# Clock_Timer.net
KiCad netlist of a schematic drawn in EAGLE
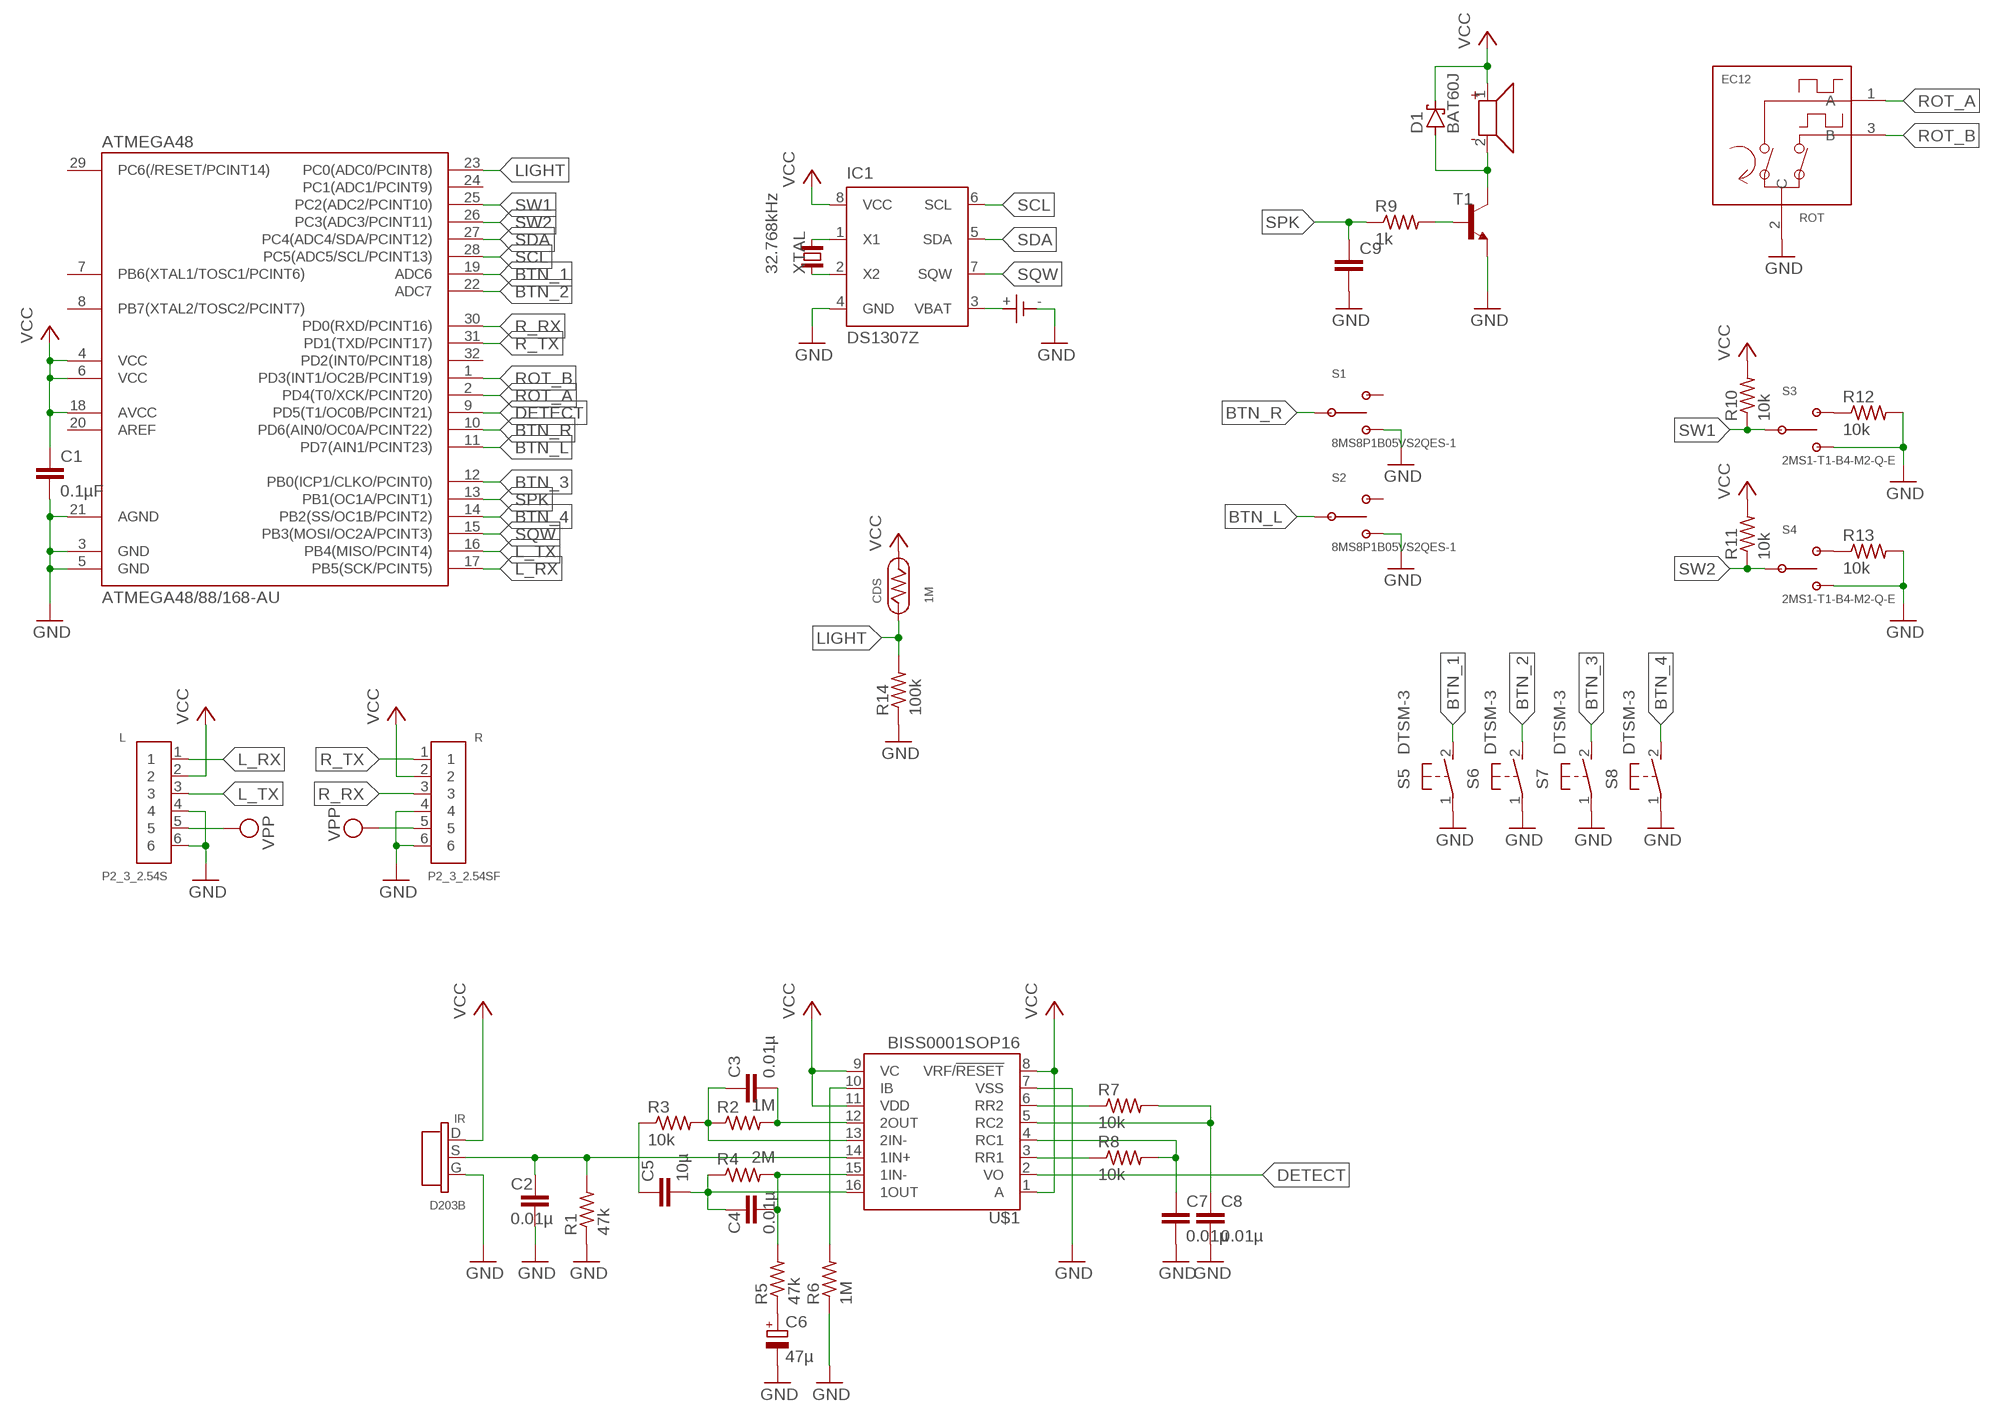
[diagram p0: schematic, sheet 1]

(export (version "E")
  (design (tool "Eeschema 10.0.6"))
  (components
    (comp (ref "ATMEGA48")
      (value "ATMEGA48/88/168-AU")
      (footprint "eagle-import:TQFP32-08")
      (libsource (lib "eagle-import") (part "ATMEGA48/88/168-AU"))
    )
    (comp (ref "BAT")
      (value "BC1/3N")
      (footprint "eagle-import:BC1_3N")
      (libsource (lib "eagle-import") (part "BC1/3N"))
    )
    (comp (ref "C1")
      (value "0.1µF")
      (footprint "eagle-import:C0603")
      (libsource (lib "eagle-import") (part "C-EUC0603"))
    )
    (comp (ref "C2")
      (value "0.01µ")
      (footprint "eagle-import:C0603")
      (libsource (lib "eagle-import") (part "resistor_348_C-EUC0603"))
    )
    (comp (ref "C3")
      (value "0.01µ")
      (footprint "eagle-import:C0603")
      (libsource (lib "eagle-import") (part "resistor_348_C-EUC0603"))
    )
    (comp (ref "C4")
      (value "0.01µ")
      (footprint "eagle-import:C0603")
      (libsource (lib "eagle-import") (part "resistor_348_C-EUC0603"))
    )
    (comp (ref "C5")
      (value "10µ")
      (footprint "eagle-import:C0603")
      (libsource (lib "eagle-import") (part "resistor_348_C-EUC0603"))
    )
    (comp (ref "C6")
      (value "47µ")
      (footprint "eagle-import:153CLV-0605")
      (libsource (lib "eagle-import") (part "CPOL-EU153CLV-0605"))
    )
    (comp (ref "C7")
      (value "0.01µ")
      (footprint "eagle-import:C0603")
      (libsource (lib "eagle-import") (part "resistor_348_C-EUC0603"))
    )
    (comp (ref "C8")
      (value "0.01µ")
      (footprint "eagle-import:C0603")
      (libsource (lib "eagle-import") (part "resistor_348_C-EUC0603"))
    )
    (comp (ref "C9")
      (value "C-EUC0603")
      (footprint "eagle-import:C0603")
      (libsource (lib "eagle-import") (part "resistor_348_C-EUC0603"))
    )
    (comp (ref "CDS")
      (value "1M")
      (footprint "eagle-import:GL55")
      (libsource (lib "eagle-import") (part "GL55"))
    )
    (comp (ref "D1")
      (value "BAT60J")
      (footprint "eagle-import:SOD323_ST")
      (libsource (lib "eagle-import") (part "BAT60J"))
    )
    (comp (ref "IC1")
      (value "DS1307Z")
      (footprint "eagle-import:SOIC8")
      (libsource (lib "eagle-import") (part "DS1307Z"))
    )
    (comp (ref "IR")
      (value "D203B")
      (footprint "eagle-import:D203B")
      (libsource (lib "eagle-import") (part "D203B"))
    )
    (comp (ref "L")
      (value "P2_3_2.54S")
      (footprint "eagle-import:P2_3_2.54S")
      (libsource (lib "eagle-import") (part "P2_3_2.54S"))
    )
    (comp (ref "R")
      (value "P2_3_2.54SF")
      (footprint "eagle-import:P2_3_2.54SF")
      (libsource (lib "eagle-import") (part "P2_3_2.54SF"))
    )
    (comp (ref "R1")
      (value "47k")
      (footprint "eagle-import:R0603")
      (libsource (lib "eagle-import") (part "R-US_R0603"))
    )
    (comp (ref "R2")
      (value "1M")
      (footprint "eagle-import:R0603")
      (libsource (lib "eagle-import") (part "R-US_R0603"))
    )
    (comp (ref "R3")
      (value "10k")
      (footprint "eagle-import:R0603")
      (libsource (lib "eagle-import") (part "R-US_R0603"))
    )
    (comp (ref "R4")
      (value "2M")
      (footprint "eagle-import:R0603")
      (libsource (lib "eagle-import") (part "R-US_R0603"))
    )
    (comp (ref "R5")
      (value "47k")
      (footprint "eagle-import:R0603")
      (libsource (lib "eagle-import") (part "R-US_R0603"))
    )
    (comp (ref "R6")
      (value "1M")
      (footprint "eagle-import:R0603")
      (libsource (lib "eagle-import") (part "R-US_R0603"))
    )
    (comp (ref "R7")
      (value "10k")
      (footprint "eagle-import:R0603")
      (libsource (lib "eagle-import") (part "R-US_R0603"))
    )
    (comp (ref "R8")
      (value "10k")
      (footprint "eagle-import:R0603")
      (libsource (lib "eagle-import") (part "R-US_R0603"))
    )
    (comp (ref "R9")
      (value "1k")
      (footprint "eagle-import:R0603")
      (libsource (lib "eagle-import") (part "resistor_348_R-US_R0603"))
    )
    (comp (ref "R10")
      (value "10k")
      (footprint "eagle-import:R0603")
      (libsource (lib "eagle-import") (part "R-US_R0603"))
    )
    (comp (ref "R11")
      (value "10k")
      (footprint "eagle-import:R0603")
      (libsource (lib "eagle-import") (part "R-US_R0603"))
    )
    (comp (ref "R12")
      (value "10k")
      (footprint "eagle-import:R0603")
      (libsource (lib "eagle-import") (part "R-US_R0603"))
    )
    (comp (ref "R13")
      (value "10k")
      (footprint "eagle-import:R0603")
      (libsource (lib "eagle-import") (part "R-US_R0603"))
    )
    (comp (ref "R14")
      (value "100k")
      (footprint "eagle-import:R0603")
      (libsource (lib "eagle-import") (part "R-US_R0603"))
    )
    (comp (ref "ROT")
      (value "EC12")
      (footprint "eagle-import:EC12")
      (libsource (lib "eagle-import") (part "EC12"))
    )
    (comp (ref "S1")
      (value "8MS8P1B05VS2QES-1")
      (footprint "eagle-import:8MS8P1B05VS2QES-1")
      (libsource (lib "eagle-import") (part "8MS8P1B05VS2QES-1"))
    )
    (comp (ref "S2")
      (value "8MS8P1B05VS2QES-1")
      (footprint "eagle-import:8MS8P1B05VS2QES-1")
      (libsource (lib "eagle-import") (part "8MS8P1B05VS2QES-1"))
    )
    (comp (ref "S3")
      (value "2MS1-T1-B4-M2-Q-E")
      (footprint "eagle-import:2MS1-T1-B4-M2-Q-E")
      (libsource (lib "eagle-import") (part "2MS1-T1-B4-M2-Q-E"))
    )
    (comp (ref "S4")
      (value "2MS1-T1-B4-M2-Q-E")
      (footprint "eagle-import:2MS1-T1-B4-M2-Q-E")
      (libsource (lib "eagle-import") (part "2MS1-T1-B4-M2-Q-E"))
    )
    (comp (ref "S5")
      (value "DTSM-3")
      (footprint "eagle-import:DTSM-3")
      (libsource (lib "eagle-import") (part "DTSM-3"))
    )
    (comp (ref "S6")
      (value "DTSM-3")
      (footprint "eagle-import:DTSM-3")
      (libsource (lib "eagle-import") (part "DTSM-3"))
    )
    (comp (ref "S7")
      (value "DTSM-3")
      (footprint "eagle-import:DTSM-3")
      (libsource (lib "eagle-import") (part "DTSM-3"))
    )
    (comp (ref "S8")
      (value "DTSM-3")
      (footprint "eagle-import:DTSM-3")
      (libsource (lib "eagle-import") (part "DTSM-3"))
    )
    (comp (ref "T1")
      (value "-NPN-SOT23-EBC")
      (footprint "eagle-import:SOT23-EBC")
      (libsource (lib "eagle-import") (part "-NPN-SOT23-EBC"))
    )
    (comp (ref "U$1")
      (value "BISS0001SOP16")
      (footprint "eagle-import:SOP16")
      (libsource (lib "eagle-import") (part "BISS0001SOP16"))
    )
    (comp (ref "U$9")
      (value "UGCM0903EPD")
      (footprint "eagle-import:UGCM0903EPD")
      (libsource (lib "eagle-import") (part "UGCM0903EPD"))
    )
    (comp (ref "XTAL")
      (value "32.768kHz")
      (footprint "eagle-import:FC-255")
      (libsource (lib "eagle-import") (part "CRYTALFC-255"))
    )
  )
  (nets
    (net (code "1") (name "BTN_1") (class "Default")
      (node (ref "ATMEGA48") (pin "19") (pinfunction "ADC6_19") (pintype "passive"))
      (node (ref "S5") (pin "2") (pinfunction "2_2") (pintype "passive"))
    )
    (net (code "2") (name "BTN_2") (class "Default")
      (node (ref "ATMEGA48") (pin "22") (pinfunction "ADC7_22") (pintype "passive"))
      (node (ref "S6") (pin "2") (pinfunction "2_2") (pintype "passive"))
    )
    (net (code "3") (name "BTN_3") (class "Default")
      (node (ref "ATMEGA48") (pin "12") (pinfunction "PB0(ICP1/CLKO/PCINT0)_12") (pintype "bidirectional"))
      (node (ref "S7") (pin "2") (pinfunction "2_2") (pintype "passive"))
    )
    (net (code "4") (name "BTN_4") (class "Default")
      (node (ref "ATMEGA48") (pin "14") (pinfunction "PB2(SS/OC1B/PCINT2)_14") (pintype "bidirectional"))
      (node (ref "S8") (pin "2") (pinfunction "2_2") (pintype "passive"))
    )
    (net (code "5") (name "BTN_L") (class "Default")
      (node (ref "ATMEGA48") (pin "11") (pinfunction "PD7(AIN1/PCINT23)_11") (pintype "bidirectional"))
      (node (ref "S2") (pin "2") (pinfunction "C_2") (pintype "bidirectional"))
    )
    (net (code "6") (name "BTN_R") (class "Default")
      (node (ref "ATMEGA48") (pin "10") (pinfunction "PD6(AIN0/OC0A/PCINT22)_10") (pintype "bidirectional"))
      (node (ref "S1") (pin "2") (pinfunction "C_2") (pintype "bidirectional"))
    )
    (net (code "7") (name "DETECT") (class "Default")
      (node (ref "ATMEGA48") (pin "9") (pinfunction "PD5(T1/OC0B/PCINT21)_9") (pintype "bidirectional"))
      (node (ref "U$1") (pin "2") (pinfunction "VO_2") (pintype "bidirectional"))
    )
    (net (code "8") (name "GND") (class "Default")
      (node (ref "ATMEGA48") (pin "21") (pinfunction "AGND_21") (pintype "power_in"))
      (node (ref "ATMEGA48") (pin "3") (pinfunction "GND_3") (pintype "power_in"))
      (node (ref "ATMEGA48") (pin "5") (pinfunction "GND_5") (pintype "power_in"))
      (node (ref "BAT") (pin "-") (pinfunction "V-_-") (pintype "power_in"))
      (node (ref "C1") (pin "2") (pinfunction "2_2") (pintype "passive"))
      (node (ref "C2") (pin "2") (pinfunction "2_2") (pintype "passive"))
      (node (ref "C6") (pin "-") (pinfunction "-_-") (pintype "passive"))
      (node (ref "C7") (pin "2") (pinfunction "2_2") (pintype "passive"))
      (node (ref "C8") (pin "2") (pinfunction "2_2") (pintype "passive"))
      (node (ref "C9") (pin "2") (pinfunction "2_2") (pintype "passive"))
      (node (ref "IC1") (pin "4") (pinfunction "GND_4") (pintype "power_in"))
      (node (ref "IR") (pin "G") (pinfunction "GND_G") (pintype "bidirectional"))
      (node (ref "L") (pin "4") (pinfunction "4_4") (pintype "bidirectional"))
      (node (ref "L") (pin "6") (pinfunction "6_6") (pintype "bidirectional"))
      (node (ref "R") (pin "4") (pinfunction "4_4") (pintype "bidirectional"))
      (node (ref "R") (pin "6") (pinfunction "6_6") (pintype "bidirectional"))
      (node (ref "R1") (pin "1") (pinfunction "1_1") (pintype "passive"))
      (node (ref "R12") (pin "2") (pinfunction "2_2") (pintype "passive"))
      (node (ref "R13") (pin "2") (pinfunction "2_2") (pintype "passive"))
      (node (ref "R14") (pin "1") (pinfunction "1_1") (pintype "passive"))
      (node (ref "R6") (pin "1") (pinfunction "1_1") (pintype "passive"))
      (node (ref "ROT") (pin "2") (pinfunction "C_2") (pintype "bidirectional"))
      (node (ref "S1") (pin "3") (pinfunction "B_3") (pintype "bidirectional"))
      (node (ref "S2") (pin "3") (pinfunction "B_3") (pintype "bidirectional"))
      (node (ref "S3") (pin "3") (pinfunction "B_3") (pintype "bidirectional"))
      (node (ref "S4") (pin "3") (pinfunction "B_3") (pintype "bidirectional"))
      (node (ref "S5") (pin "1") (pinfunction "1_1") (pintype "passive"))
      (node (ref "S6") (pin "1") (pinfunction "1_1") (pintype "passive"))
      (node (ref "S7") (pin "1") (pinfunction "1_1") (pintype "passive"))
      (node (ref "S8") (pin "1") (pinfunction "1_1") (pintype "passive"))
      (node (ref "T1") (pin "E") (pinfunction "E_E") (pintype "passive"))
      (node (ref "U$1") (pin "7") (pinfunction "VSS_7") (pintype "bidirectional"))
    )
    (net (code "9") (name "LIGHT") (class "Default")
      (node (ref "ATMEGA48") (pin "23") (pinfunction "PC0(ADC0/PCINT8)_23") (pintype "bidirectional"))
      (node (ref "CDS") (pin "1") (pinfunction "P$1_1") (pintype "bidirectional"))
      (node (ref "R14") (pin "2") (pinfunction "2_2") (pintype "passive"))
    )
    (net (code "10") (name "L_RX") (class "Default")
      (node (ref "ATMEGA48") (pin "17") (pinfunction "PB5(SCK/PCINT5)_17") (pintype "bidirectional"))
      (node (ref "L") (pin "1") (pinfunction "1_1") (pintype "bidirectional"))
    )
    (net (code "11") (name "L_TX") (class "Default")
      (node (ref "ATMEGA48") (pin "16") (pinfunction "PB4(MISO/PCINT4)_16") (pintype "bidirectional"))
      (node (ref "L") (pin "3") (pinfunction "3_3") (pintype "bidirectional"))
    )
    (net (code "12") (name "Net-(BAT-V+)") (class "Default")
      (node (ref "BAT") (pin "+") (pinfunction "V+_+") (pintype "power_in"))
      (node (ref "IC1") (pin "3") (pinfunction "VBAT_3") (pintype "passive"))
    )
    (net (code "13") (name "Net-(C5-Pad1)") (class "Default")
      (node (ref "C5") (pin "1") (pinfunction "1_1") (pintype "passive"))
      (node (ref "R3") (pin "1") (pinfunction "1_1") (pintype "passive"))
    )
    (net (code "14") (name "Net-(C6-Pad+)") (class "Default")
      (node (ref "C6") (pin "+") (pinfunction "+_+") (pintype "passive"))
      (node (ref "R5") (pin "1") (pinfunction "1_1") (pintype "passive"))
    )
    (net (code "15") (name "Net-(IC1-X1)") (class "Default")
      (node (ref "IC1") (pin "1") (pinfunction "X1_1") (pintype "input"))
      (node (ref "XTAL") (pin "2") (pinfunction "2_2") (pintype "passive"))
    )
    (net (code "16") (name "Net-(IC1-X2)") (class "Default")
      (node (ref "IC1") (pin "2") (pinfunction "X2_2") (pintype "output"))
      (node (ref "XTAL") (pin "1") (pinfunction "1_1") (pintype "passive"))
    )
    (net (code "17") (name "Net-(IR-OUTPUT)") (class "Default")
      (node (ref "C2") (pin "1") (pinfunction "1_1") (pintype "passive"))
      (node (ref "IR") (pin "S") (pinfunction "OUTPUT_S") (pintype "bidirectional"))
      (node (ref "R1") (pin "2") (pinfunction "2_2") (pintype "passive"))
      (node (ref "U$1") (pin "14") (pinfunction "1IN+_14") (pintype "bidirectional"))
    )
    (net (code "18") (name "Net-(R9-Pad2)") (class "Default")
      (node (ref "R9") (pin "2") (pinfunction "2_2") (pintype "passive"))
      (node (ref "T1") (pin "B") (pinfunction "B_B") (pintype "passive"))
    )
    (net (code "19") (name "Net-(S3-A)") (class "Default")
      (node (ref "R12") (pin "1") (pinfunction "1_1") (pintype "passive"))
      (node (ref "S3") (pin "1") (pinfunction "A_1") (pintype "bidirectional"))
    )
    (net (code "20") (name "Net-(S4-A)") (class "Default")
      (node (ref "R13") (pin "1") (pinfunction "1_1") (pintype "passive"))
      (node (ref "S4") (pin "1") (pinfunction "A_1") (pintype "bidirectional"))
    )
    (net (code "21") (name "Net-(U$1-1IN-)") (class "Default")
      (node (ref "C4") (pin "2") (pinfunction "2_2") (pintype "passive"))
      (node (ref "R4") (pin "2") (pinfunction "2_2") (pintype "passive"))
      (node (ref "R5") (pin "2") (pinfunction "2_2") (pintype "passive"))
      (node (ref "U$1") (pin "15") (pinfunction "1IN-_15") (pintype "bidirectional"))
    )
    (net (code "22") (name "Net-(U$1-1OUT)") (class "Default")
      (node (ref "C4") (pin "1") (pinfunction "1_1") (pintype "passive"))
      (node (ref "C5") (pin "2") (pinfunction "2_2") (pintype "passive"))
      (node (ref "R4") (pin "1") (pinfunction "1_1") (pintype "passive"))
      (node (ref "U$1") (pin "16") (pinfunction "1OUT_16") (pintype "bidirectional"))
    )
    (net (code "23") (name "Net-(U$1-2IN-)") (class "Default")
      (node (ref "C3") (pin "1") (pinfunction "1_1") (pintype "passive"))
      (node (ref "R2") (pin "1") (pinfunction "1_1") (pintype "passive"))
      (node (ref "R3") (pin "2") (pinfunction "2_2") (pintype "passive"))
      (node (ref "U$1") (pin "13") (pinfunction "2IN-_13") (pintype "bidirectional"))
    )
    (net (code "24") (name "Net-(U$1-2OUT)") (class "Default")
      (node (ref "C3") (pin "2") (pinfunction "2_2") (pintype "passive"))
      (node (ref "R2") (pin "2") (pinfunction "2_2") (pintype "passive"))
      (node (ref "U$1") (pin "12") (pinfunction "2OUT_12") (pintype "bidirectional"))
    )
    (net (code "25") (name "Net-(U$1-IB)") (class "Default")
      (node (ref "R6") (pin "2") (pinfunction "2_2") (pintype "passive"))
      (node (ref "U$1") (pin "10") (pinfunction "IB_10") (pintype "bidirectional"))
    )
    (net (code "26") (name "Net-(U$1-RC1)") (class "Default")
      (node (ref "C7") (pin "1") (pinfunction "1_1") (pintype "passive"))
      (node (ref "R8") (pin "2") (pinfunction "2_2") (pintype "passive"))
      (node (ref "U$1") (pin "4") (pinfunction "RC1_4") (pintype "bidirectional"))
    )
    (net (code "27") (name "Net-(U$1-RC2)") (class "Default")
      (node (ref "C8") (pin "1") (pinfunction "1_1") (pintype "passive"))
      (node (ref "R7") (pin "2") (pinfunction "2_2") (pintype "passive"))
      (node (ref "U$1") (pin "5") (pinfunction "RC2_5") (pintype "bidirectional"))
    )
    (net (code "28") (name "Net-(U$1-RR1)") (class "Default")
      (node (ref "R8") (pin "1") (pinfunction "1_1") (pintype "passive"))
      (node (ref "U$1") (pin "3") (pinfunction "RR1_3") (pintype "bidirectional"))
    )
    (net (code "29") (name "Net-(U$1-RR2)") (class "Default")
      (node (ref "R7") (pin "1") (pinfunction "1_1") (pintype "passive"))
      (node (ref "U$1") (pin "6") (pinfunction "RR2_6") (pintype "bidirectional"))
    )
    (net (code "30") (name "Net-(U$9-P$2)") (class "Default")
      (node (ref "D1") (pin "A") (pinfunction "A_A") (pintype "passive"))
      (node (ref "T1") (pin "C") (pinfunction "C_C") (pintype "passive"))
      (node (ref "U$9") (pin "2") (pinfunction "P$2_2") (pintype "bidirectional"))
    )
    (net (code "31") (name "ROT_A") (class "Default")
      (node (ref "ATMEGA48") (pin "2") (pinfunction "PD4(T0/XCK/PCINT20)_2") (pintype "bidirectional"))
      (node (ref "ROT") (pin "1") (pinfunction "A_1") (pintype "bidirectional"))
    )
    (net (code "32") (name "ROT_B") (class "Default")
      (node (ref "ATMEGA48") (pin "1") (pinfunction "PD3(INT1/OC2B/PCINT19)_1") (pintype "bidirectional"))
      (node (ref "ROT") (pin "3") (pinfunction "B_3") (pintype "bidirectional"))
    )
    (net (code "33") (name "R_RX") (class "Default")
      (node (ref "ATMEGA48") (pin "30") (pinfunction "PD0(RXD/PCINT16)_30") (pintype "bidirectional"))
      (node (ref "R") (pin "3") (pinfunction "3_3") (pintype "bidirectional"))
    )
    (net (code "34") (name "R_TX") (class "Default")
      (node (ref "ATMEGA48") (pin "31") (pinfunction "PD1(TXD/PCINT17)_31") (pintype "bidirectional"))
      (node (ref "R") (pin "1") (pinfunction "1_1") (pintype "bidirectional"))
    )
    (net (code "35") (name "SCL") (class "Default")
      (node (ref "ATMEGA48") (pin "28") (pinfunction "PC5(ADC5/SCL/PCINT13)_28") (pintype "bidirectional"))
      (node (ref "IC1") (pin "6") (pinfunction "SCL_6") (pintype "input"))
    )
    (net (code "36") (name "SDA") (class "Default")
      (node (ref "ATMEGA48") (pin "27") (pinfunction "PC4(ADC4/SDA/PCINT12)_27") (pintype "bidirectional"))
      (node (ref "IC1") (pin "5") (pinfunction "SDA_5") (pintype "bidirectional"))
    )
    (net (code "37") (name "SPK") (class "Default")
      (node (ref "ATMEGA48") (pin "13") (pinfunction "PB1(OC1A/PCINT1)_13") (pintype "bidirectional"))
      (node (ref "C9") (pin "1") (pinfunction "1_1") (pintype "passive"))
      (node (ref "R9") (pin "1") (pinfunction "1_1") (pintype "passive"))
    )
    (net (code "38") (name "SQW") (class "Default")
      (node (ref "ATMEGA48") (pin "15") (pinfunction "PB3(MOSI/OC2A/PCINT3)_15") (pintype "bidirectional"))
      (node (ref "IC1") (pin "7") (pinfunction "SQW_7") (pintype "open_collector"))
    )
    (net (code "39") (name "SW1") (class "Default")
      (node (ref "ATMEGA48") (pin "25") (pinfunction "PC2(ADC2/PCINT10)_25") (pintype "bidirectional"))
      (node (ref "R10") (pin "1") (pinfunction "1_1") (pintype "passive"))
      (node (ref "S3") (pin "2") (pinfunction "C_2") (pintype "bidirectional"))
    )
    (net (code "40") (name "SW2") (class "Default")
      (node (ref "ATMEGA48") (pin "26") (pinfunction "PC3(ADC3/PCINT11)_26") (pintype "bidirectional"))
      (node (ref "R11") (pin "1") (pinfunction "1_1") (pintype "passive"))
      (node (ref "S4") (pin "2") (pinfunction "C_2") (pintype "bidirectional"))
    )
    (net (code "41") (name "VCC") (class "Default")
      (node (ref "ATMEGA48") (pin "18") (pinfunction "AVCC_18") (pintype "passive"))
      (node (ref "ATMEGA48") (pin "4") (pinfunction "VCC_4") (pintype "power_in"))
      (node (ref "ATMEGA48") (pin "6") (pinfunction "VCC_6") (pintype "power_in"))
      (node (ref "C1") (pin "1") (pinfunction "1_1") (pintype "passive"))
      (node (ref "CDS") (pin "2") (pinfunction "P$2_2") (pintype "bidirectional"))
      (node (ref "D1") (pin "C") (pinfunction "C_C") (pintype "passive"))
      (node (ref "IC1") (pin "8") (pinfunction "VCC_8") (pintype "power_in"))
      (node (ref "IR") (pin "D") (pinfunction "VIN_D") (pintype "bidirectional"))
      (node (ref "L") (pin "2") (pinfunction "2_2") (pintype "bidirectional"))
      (node (ref "R") (pin "2") (pinfunction "2_2") (pintype "bidirectional"))
      (node (ref "R10") (pin "2") (pinfunction "2_2") (pintype "passive"))
      (node (ref "R11") (pin "2") (pinfunction "2_2") (pintype "passive"))
      (node (ref "U$1") (pin "1") (pinfunction "A_1") (pintype "bidirectional"))
      (node (ref "U$1") (pin "11") (pinfunction "VDD_11") (pintype "bidirectional"))
      (node (ref "U$1") (pin "8") (pinfunction "VRF/~{RESET}_8") (pintype "bidirectional"))
      (node (ref "U$1") (pin "9") (pinfunction "VC_9") (pintype "bidirectional"))
      (node (ref "U$9") (pin "1") (pinfunction "P$1_1") (pintype "bidirectional"))
    )
    (net (code "42") (name "VPP") (class "Default")
      (node (ref "L") (pin "5") (pinfunction "5_5") (pintype "bidirectional"))
      (node (ref "R") (pin "5") (pinfunction "5_5") (pintype "bidirectional"))
    )
    (net (code "43") (name "unconnected-(ATMEGA48-AREF-Pad20)") (class "Default")
      (node (ref "ATMEGA48") (pin "20") (pinfunction "AREF_20") (pintype "passive"))
    )
    (net (code "44") (name "unconnected-(ATMEGA48-PB6(XTAL1{slash}TOSC1{slash}PCINT6)-Pad7)") (class "Default")
      (node (ref "ATMEGA48") (pin "7") (pinfunction "PB6(XTAL1/TOSC1/PCINT6)_7") (pintype "bidirectional"))
    )
    (net (code "45") (name "unconnected-(ATMEGA48-PB7(XTAL2{slash}TOSC2{slash}PCINT7)-Pad8)") (class "Default")
      (node (ref "ATMEGA48") (pin "8") (pinfunction "PB7(XTAL2/TOSC2/PCINT7)_8") (pintype "bidirectional"))
    )
    (net (code "46") (name "unconnected-(ATMEGA48-PC1(ADC1{slash}PCINT9)-Pad24)") (class "Default")
      (node (ref "ATMEGA48") (pin "24") (pinfunction "PC1(ADC1/PCINT9)_24") (pintype "bidirectional"))
    )
    (net (code "47") (name "unconnected-(ATMEGA48-PC6({slash}RESET{slash}PCINT14)-Pad29)") (class "Default")
      (node (ref "ATMEGA48") (pin "29") (pinfunction "PC6(/RESET/PCINT14)_29") (pintype "bidirectional"))
    )
    (net (code "48") (name "unconnected-(ATMEGA48-PD2(INT0{slash}PCINT18)-Pad32)") (class "Default")
      (node (ref "ATMEGA48") (pin "32") (pinfunction "PD2(INT0/PCINT18)_32") (pintype "bidirectional"))
    )
    (net (code "49") (name "unconnected-(S1-A-Pad1)") (class "Default")
      (node (ref "S1") (pin "1") (pinfunction "A_1") (pintype "bidirectional"))
    )
    (net (code "50") (name "unconnected-(S2-A-Pad1)") (class "Default")
      (node (ref "S2") (pin "1") (pinfunction "A_1") (pintype "bidirectional"))
    )
  )
)
